# guitar_tuner_amplifier.net
KiCad netlist of a schematic drawn in EAGLE
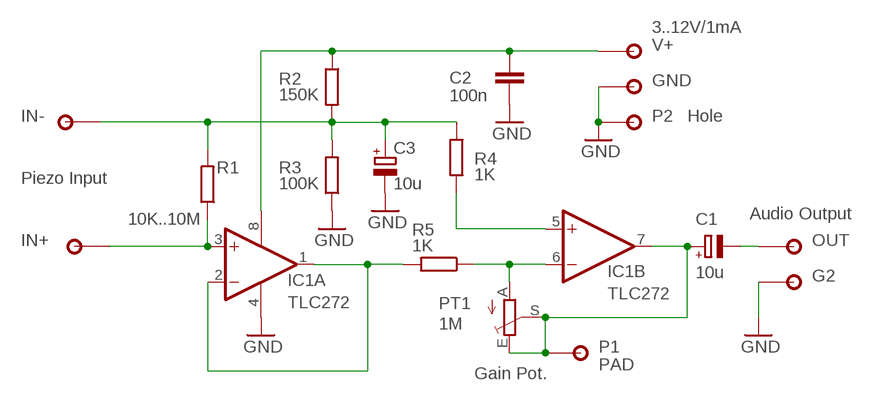
[diagram p0: schematic, sheet 1]

(export (version "E")
  (design (tool "Eeschema 10.0.6"))
  (components
    (comp (ref "C1")
      (value "10u")
      (footprint "eagle-import:E2,5-5")
      (libsource (lib "eagle-import") (part "CPOL-EUE2.5-5"))
    )
    (comp (ref "C2")
      (value "100n")
      (footprint "eagle-import:C025-025X050")
      (libsource (lib "eagle-import") (part "C-EU025-025X050"))
    )
    (comp (ref "C3")
      (value "10u")
      (footprint "eagle-import:E2,5-5")
      (libsource (lib "eagle-import") (part "CPOL-EUE2.5-5"))
    )
    (comp (ref "G2")
      (value "PAD1,46MM")
      (footprint "eagle-import:PAD146")
      (libsource (lib "eagle-import") (part "PAD1,46MM"))
    )
    (comp (ref "GND")
      (value "PAD1,46MM")
      (footprint "eagle-import:PAD146")
      (libsource (lib "eagle-import") (part "PAD1,46MM"))
    )
    (comp (ref "IC1")
      (value "TLC272")
      (footprint "eagle-import:DIL08")
      (libsource (lib "eagle-import") (part "TLC272P"))
    )
    (comp (ref "IN+")
      (value "PAD1,46MM")
      (footprint "eagle-import:PAD146")
      (libsource (lib "eagle-import") (part "PAD1,46MM"))
    )
    (comp (ref "IN-")
      (value "PAD1,46MM")
      (footprint "eagle-import:PAD146")
      (libsource (lib "eagle-import") (part "PAD1,46MM"))
    )
    (comp (ref "OUT")
      (value "PAD1,46MM")
      (footprint "eagle-import:PAD146")
      (libsource (lib "eagle-import") (part "PAD1,46MM"))
    )
    (comp (ref "P1")
      (value "PAD")
      (footprint "eagle-import:PAD127L1")
      (libsource (lib "eagle-import") (part "PADL2"))
    )
    (comp (ref "P2")
      (value "Hole")
      (footprint "eagle-import:PAD146")
      (libsource (lib "eagle-import") (part "PAD1,46MM"))
    )
    (comp (ref "PT1")
      (value "1M")
      (footprint "eagle-import:CA6V")
      (libsource (lib "eagle-import") (part "TRIM_EU-CA6V"))
    )
    (comp (ref "R1")
      (value "10K..10M")
      (footprint "eagle-import:0207_10")
      (libsource (lib "eagle-import") (part "R-EU_0207/10"))
    )
    (comp (ref "R2")
      (value "150K")
      (footprint "eagle-import:0207_10")
      (libsource (lib "eagle-import") (part "R-EU_0207/10"))
    )
    (comp (ref "R3")
      (value "100K")
      (footprint "eagle-import:0207_10")
      (libsource (lib "eagle-import") (part "R-EU_0207/10"))
    )
    (comp (ref "R4")
      (value "1K")
      (footprint "eagle-import:0207_10")
      (libsource (lib "eagle-import") (part "R-EU_0207/10"))
    )
    (comp (ref "R5")
      (value "1K")
      (footprint "eagle-import:0207_10")
      (libsource (lib "eagle-import") (part "R-EU_0207/10"))
    )
    (comp (ref "V+")
      (value "PAD1,46MM")
      (footprint "eagle-import:PAD146")
      (libsource (lib "eagle-import") (part "PAD1,46MM"))
    )
  )
  (nets
    (net (code "1") (name "GND") (class "Default")
      (node (ref "C2") (pin "1") (pinfunction "1_1") (pintype "passive"))
      (node (ref "C3") (pin "-") (pinfunction "-_-") (pintype "passive"))
      (node (ref "G2") (pin "1") (pinfunction "1_1") (pintype "passive"))
      (node (ref "GND") (pin "1") (pinfunction "1_1") (pintype "passive"))
      (node (ref "IC1") (pin "4") (pinfunction "V-_4") (pintype "power_in"))
      (node (ref "P2") (pin "1") (pinfunction "1_1") (pintype "passive"))
      (node (ref "R3") (pin "1") (pinfunction "1_1") (pintype "passive"))
    )
    (net (code "2") (name "Net-(C1-Pad-)") (class "Default")
      (node (ref "C1") (pin "-") (pinfunction "-_-") (pintype "passive"))
      (node (ref "OUT") (pin "1") (pinfunction "1_1") (pintype "passive"))
    )
    (net (code "3") (name "Net-(C3-Pad+)") (class "Default")
      (node (ref "C3") (pin "+") (pinfunction "+_+") (pintype "passive"))
      (node (ref "IN-") (pin "1") (pinfunction "1_1") (pintype "passive"))
      (node (ref "R1") (pin "2") (pinfunction "2_2") (pintype "passive"))
      (node (ref "R2") (pin "2") (pinfunction "2_2") (pintype "passive"))
      (node (ref "R3") (pin "2") (pinfunction "2_2") (pintype "passive"))
      (node (ref "R4") (pin "2") (pinfunction "2_2") (pintype "passive"))
    )
    (net (code "4") (name "Net-(IC1A-+IN)") (class "Default")
      (node (ref "IC1") (pin "3") (pinfunction "+IN_3") (pintype "input"))
      (node (ref "IN+") (pin "1") (pinfunction "1_1") (pintype "passive"))
      (node (ref "R1") (pin "1") (pinfunction "1_1") (pintype "passive"))
    )
    (net (code "5") (name "Net-(IC1A--IN)") (class "Default")
      (node (ref "IC1") (pin "1") (pinfunction "OUT_1") (pintype "output"))
      (node (ref "IC1") (pin "2") (pinfunction "-IN_2") (pintype "input"))
      (node (ref "R5") (pin "2") (pinfunction "2_2") (pintype "passive"))
    )
    (net (code "6") (name "Net-(IC1B-+IN)") (class "Default")
      (node (ref "IC1") (pin "5") (pinfunction "+IN_5") (pintype "input"))
      (node (ref "R4") (pin "1") (pinfunction "1_1") (pintype "passive"))
    )
    (net (code "7") (name "Net-(IC1B--IN)") (class "Default")
      (node (ref "IC1") (pin "6") (pinfunction "-IN_6") (pintype "input"))
      (node (ref "PT1") (pin "A") (pinfunction "A_A") (pintype "passive"))
      (node (ref "R5") (pin "1") (pinfunction "1_1") (pintype "passive"))
    )
    (net (code "8") (name "Net-(IC1B-OUT)") (class "Default")
      (node (ref "C1") (pin "+") (pinfunction "+_+") (pintype "passive"))
      (node (ref "IC1") (pin "7") (pinfunction "OUT_7") (pintype "output"))
      (node (ref "P1") (pin "P$2") (pinfunction "1_P$2") (pintype "passive"))
      (node (ref "PT1") (pin "E") (pinfunction "E_E") (pintype "passive"))
      (node (ref "PT1") (pin "S") (pinfunction "S_S") (pintype "passive"))
    )
    (net (code "9") (name "Net-(IC1C-V+)") (class "Default")
      (node (ref "C2") (pin "2") (pinfunction "2_2") (pintype "passive"))
      (node (ref "IC1") (pin "8") (pinfunction "V+_8") (pintype "power_in"))
      (node (ref "R2") (pin "1") (pinfunction "1_1") (pintype "passive"))
      (node (ref "V+") (pin "1") (pinfunction "1_1") (pintype "passive"))
    )
  )
)
